# sensor_pcb.net
KiCad netlist of a schematic drawn in EAGLE
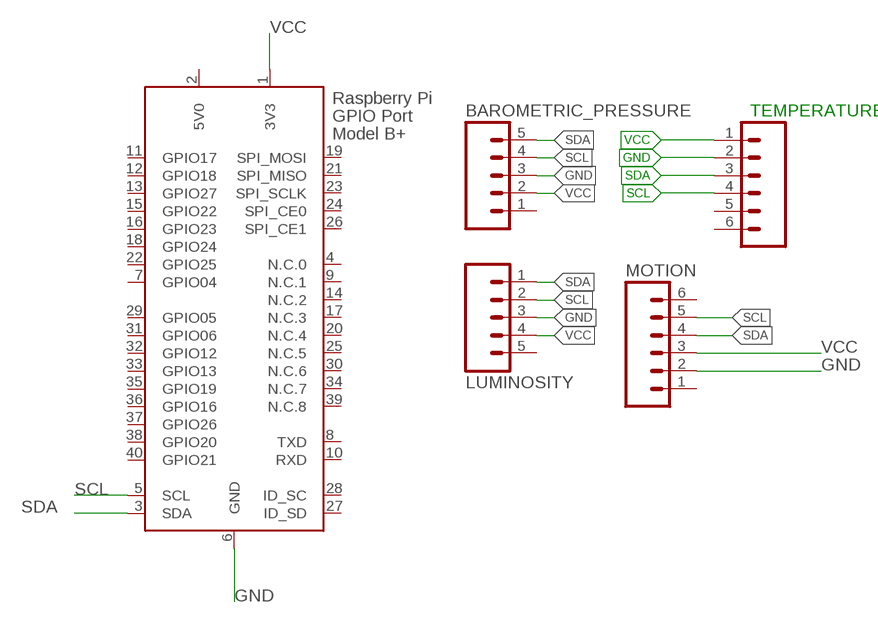
[diagram p0: schematic, sheet 1]

(export (version "E")
  (design (tool "Eeschema 10.0.6"))
  (components
    (comp (ref "BAROMETRIC_PRESSURE")
      (value "M05_ROUNDONLY_NOSILK")
      (footprint "eagle-import:1X05_ROUNDONLY_NOSILK")
      (libsource (lib "eagle-import") (part "M05_ROUNDONLY_NOSILK"))
    )
    (comp (ref "LUMINOSITY")
      (value "M05_ROUNDONLY_NOSILK")
      (footprint "eagle-import:1X05_ROUNDONLY_NOSILK")
      (libsource (lib "eagle-import") (part "M05_ROUNDONLY_NOSILK"))
    )
    (comp (ref "MOTION")
      (value "M06SIP")
      (footprint "eagle-import:1X06")
      (libsource (lib "eagle-import") (part "SparkFun-Connectors_M06SIP"))
    )
    (comp (ref "TEMPERATURE")
      (value "M06SIP")
      (footprint "eagle-import:1X06")
      (libsource (lib "eagle-import") (part "M06SIP"))
    )
    (comp (ref "X1")
      (value "RASPI_BOARD_B+_E0")
      (footprint "eagle-import:RASPI_BOARD_B+_EDGES_0DRILL")
      (libsource (lib "eagle-import") (part "RASPI_BOARD_B+_E0"))
    )
  )
  (nets
    (net (code "1") (name "/5V0") (class "Default")
      (node (ref "X1") (pin "2") (pinfunction "5V0_2") (pintype "power_in"))
    )
    (net (code "2") (name "GND") (class "Default")
      (node (ref "BAROMETRIC_PRESSURE") (pin "3") (pinfunction "3_3") (pintype "passive"))
      (node (ref "LUMINOSITY") (pin "3") (pinfunction "3_3") (pintype "passive"))
      (node (ref "MOTION") (pin "2") (pinfunction "2_2") (pintype "passive"))
      (node (ref "TEMPERATURE") (pin "2") (pinfunction "2_2") (pintype "passive"))
      (node (ref "X1") (pin "6") (pinfunction "GND_6") (pintype "power_in"))
    )
    (net (code "3") (name "SCL") (class "Default")
      (node (ref "BAROMETRIC_PRESSURE") (pin "4") (pinfunction "4_4") (pintype "passive"))
      (node (ref "LUMINOSITY") (pin "2") (pinfunction "2_2") (pintype "passive"))
      (node (ref "MOTION") (pin "5") (pinfunction "5_5") (pintype "passive"))
      (node (ref "TEMPERATURE") (pin "4") (pinfunction "4_4") (pintype "passive"))
      (node (ref "X1") (pin "5") (pinfunction "SCL_5") (pintype "bidirectional"))
    )
    (net (code "4") (name "SDA") (class "Default")
      (node (ref "BAROMETRIC_PRESSURE") (pin "5") (pinfunction "5_5") (pintype "passive"))
      (node (ref "LUMINOSITY") (pin "1") (pinfunction "1_1") (pintype "passive"))
      (node (ref "MOTION") (pin "4") (pinfunction "4_4") (pintype "passive"))
      (node (ref "TEMPERATURE") (pin "3") (pinfunction "3_3") (pintype "passive"))
      (node (ref "X1") (pin "3") (pinfunction "SDA_3") (pintype "bidirectional"))
    )
    (net (code "5") (name "VCC") (class "Default")
      (node (ref "BAROMETRIC_PRESSURE") (pin "2") (pinfunction "2_2") (pintype "passive"))
      (node (ref "LUMINOSITY") (pin "4") (pinfunction "4_4") (pintype "passive"))
      (node (ref "MOTION") (pin "3") (pinfunction "3_3") (pintype "passive"))
      (node (ref "TEMPERATURE") (pin "1") (pinfunction "1_1") (pintype "passive"))
      (node (ref "X1") (pin "1") (pinfunction "3V3_1") (pintype "power_in"))
    )
    (net (code "6") (name "unconnected-(BAROMETRIC_PRESSURE-Pad1)") (class "Default")
      (node (ref "BAROMETRIC_PRESSURE") (pin "1") (pinfunction "1_1") (pintype "passive"))
    )
    (net (code "7") (name "unconnected-(LUMINOSITY-Pad5)") (class "Default")
      (node (ref "LUMINOSITY") (pin "5") (pinfunction "5_5") (pintype "passive"))
    )
    (net (code "8") (name "unconnected-(MOTION-Pad1)") (class "Default")
      (node (ref "MOTION") (pin "1") (pinfunction "1_1") (pintype "passive"))
    )
    (net (code "9") (name "unconnected-(MOTION-Pad6)") (class "Default")
      (node (ref "MOTION") (pin "6") (pinfunction "6_6") (pintype "passive"))
    )
    (net (code "10") (name "unconnected-(TEMPERATURE-Pad5)") (class "Default")
      (node (ref "TEMPERATURE") (pin "5") (pinfunction "5_5") (pintype "passive"))
    )
    (net (code "11") (name "unconnected-(TEMPERATURE-Pad6)") (class "Default")
      (node (ref "TEMPERATURE") (pin "6") (pinfunction "6_6") (pintype "passive"))
    )
    (net (code "12") (name "unconnected-(X1-GPIO04-Pad7)") (class "Default")
      (node (ref "X1") (pin "7") (pinfunction "GPIO04_7") (pintype "bidirectional"))
    )
    (net (code "13") (name "unconnected-(X1-GPIO05-Pad29)") (class "Default")
      (node (ref "X1") (pin "29") (pinfunction "GPIO05_29") (pintype "no_connect"))
    )
    (net (code "14") (name "unconnected-(X1-GPIO06-Pad31)") (class "Default")
      (node (ref "X1") (pin "31") (pinfunction "GPIO06_31") (pintype "no_connect"))
    )
    (net (code "15") (name "unconnected-(X1-GPIO12-Pad32)") (class "Default")
      (node (ref "X1") (pin "32") (pinfunction "GPIO12_32") (pintype "no_connect"))
    )
    (net (code "16") (name "unconnected-(X1-GPIO13-Pad33)") (class "Default")
      (node (ref "X1") (pin "33") (pinfunction "GPIO13_33") (pintype "no_connect"))
    )
    (net (code "17") (name "unconnected-(X1-GPIO16-Pad36)") (class "Default")
      (node (ref "X1") (pin "36") (pinfunction "GPIO16_36") (pintype "no_connect"))
    )
    (net (code "18") (name "unconnected-(X1-GPIO17-Pad11)") (class "Default")
      (node (ref "X1") (pin "11") (pinfunction "GPIO17_11") (pintype "bidirectional"))
    )
    (net (code "19") (name "unconnected-(X1-GPIO18-Pad12)") (class "Default")
      (node (ref "X1") (pin "12") (pinfunction "GPIO18_12") (pintype "bidirectional"))
    )
    (net (code "20") (name "unconnected-(X1-GPIO19-Pad35)") (class "Default")
      (node (ref "X1") (pin "35") (pinfunction "GPIO19_35") (pintype "no_connect"))
    )
    (net (code "21") (name "unconnected-(X1-GPIO20-Pad38)") (class "Default")
      (node (ref "X1") (pin "38") (pinfunction "GPIO20_38") (pintype "no_connect"))
    )
    (net (code "22") (name "unconnected-(X1-GPIO21-Pad40)") (class "Default")
      (node (ref "X1") (pin "40") (pinfunction "GPIO21_40") (pintype "no_connect"))
    )
    (net (code "23") (name "unconnected-(X1-GPIO22-Pad15)") (class "Default")
      (node (ref "X1") (pin "15") (pinfunction "GPIO22_15") (pintype "bidirectional"))
    )
    (net (code "24") (name "unconnected-(X1-GPIO23-Pad16)") (class "Default")
      (node (ref "X1") (pin "16") (pinfunction "GPIO23_16") (pintype "bidirectional"))
    )
    (net (code "25") (name "unconnected-(X1-GPIO24-Pad18)") (class "Default")
      (node (ref "X1") (pin "18") (pinfunction "GPIO24_18") (pintype "bidirectional"))
    )
    (net (code "26") (name "unconnected-(X1-GPIO25-Pad22)") (class "Default")
      (node (ref "X1") (pin "22") (pinfunction "GPIO25_22") (pintype "bidirectional"))
    )
    (net (code "27") (name "unconnected-(X1-GPIO26-Pad37)") (class "Default")
      (node (ref "X1") (pin "37") (pinfunction "GPIO26_37") (pintype "no_connect"))
    )
    (net (code "28") (name "unconnected-(X1-GPIO27-Pad13)") (class "Default")
      (node (ref "X1") (pin "13") (pinfunction "GPIO27_13") (pintype "bidirectional"))
    )
    (net (code "29") (name "unconnected-(X1-ID_SC-Pad28)") (class "Default")
      (node (ref "X1") (pin "28") (pinfunction "ID_SC_28") (pintype "no_connect"))
    )
    (net (code "30") (name "unconnected-(X1-ID_SD-Pad27)") (class "Default")
      (node (ref "X1") (pin "27") (pinfunction "ID_SD_27") (pintype "no_connect"))
    )
    (net (code "31") (name "unconnected-(X1-N.C.0-Pad4)") (class "Default")
      (node (ref "X1") (pin "4") (pinfunction "N.C.0_4") (pintype "no_connect"))
    )
    (net (code "32") (name "unconnected-(X1-N.C.1-Pad9)") (class "Default")
      (node (ref "X1") (pin "9") (pinfunction "N.C.1_9") (pintype "no_connect"))
    )
    (net (code "33") (name "unconnected-(X1-N.C.2-Pad14)") (class "Default")
      (node (ref "X1") (pin "14") (pinfunction "N.C.2_14") (pintype "no_connect"))
    )
    (net (code "34") (name "unconnected-(X1-N.C.3-Pad17)") (class "Default")
      (node (ref "X1") (pin "17") (pinfunction "N.C.3_17") (pintype "no_connect"))
    )
    (net (code "35") (name "unconnected-(X1-N.C.4-Pad20)") (class "Default")
      (node (ref "X1") (pin "20") (pinfunction "N.C.4_20") (pintype "no_connect"))
    )
    (net (code "36") (name "unconnected-(X1-N.C.5-Pad25)") (class "Default")
      (node (ref "X1") (pin "25") (pinfunction "N.C.5_25") (pintype "no_connect"))
    )
    (net (code "37") (name "unconnected-(X1-N.C.6-Pad30)") (class "Default")
      (node (ref "X1") (pin "30") (pinfunction "N.C.6_30") (pintype "no_connect"))
    )
    (net (code "38") (name "unconnected-(X1-N.C.7-Pad34)") (class "Default")
      (node (ref "X1") (pin "34") (pinfunction "N.C.7_34") (pintype "no_connect"))
    )
    (net (code "39") (name "unconnected-(X1-N.C.8-Pad39)") (class "Default")
      (node (ref "X1") (pin "39") (pinfunction "N.C.8_39") (pintype "no_connect"))
    )
    (net (code "40") (name "unconnected-(X1-RXD-Pad10)") (class "Default")
      (node (ref "X1") (pin "10") (pinfunction "RXD_10") (pintype "bidirectional"))
    )
    (net (code "41") (name "unconnected-(X1-SPI_CE0-Pad24)") (class "Default")
      (node (ref "X1") (pin "24") (pinfunction "SPI_CE0_24") (pintype "bidirectional"))
    )
    (net (code "42") (name "unconnected-(X1-SPI_CE1-Pad26)") (class "Default")
      (node (ref "X1") (pin "26") (pinfunction "SPI_CE1_26") (pintype "bidirectional"))
    )
    (net (code "43") (name "unconnected-(X1-SPI_MISO-Pad21)") (class "Default")
      (node (ref "X1") (pin "21") (pinfunction "SPI_MISO_21") (pintype "bidirectional"))
    )
    (net (code "44") (name "unconnected-(X1-SPI_MOSI-Pad19)") (class "Default")
      (node (ref "X1") (pin "19") (pinfunction "SPI_MOSI_19") (pintype "bidirectional"))
    )
    (net (code "45") (name "unconnected-(X1-SPI_SCLK-Pad23)") (class "Default")
      (node (ref "X1") (pin "23") (pinfunction "SPI_SCLK_23") (pintype "bidirectional"))
    )
    (net (code "46") (name "unconnected-(X1-TXD-Pad8)") (class "Default")
      (node (ref "X1") (pin "8") (pinfunction "TXD_8") (pintype "bidirectional"))
    )
  )
)
